# Sheet1.net
KiCad netlist of a schematic drawn in Altium Designer
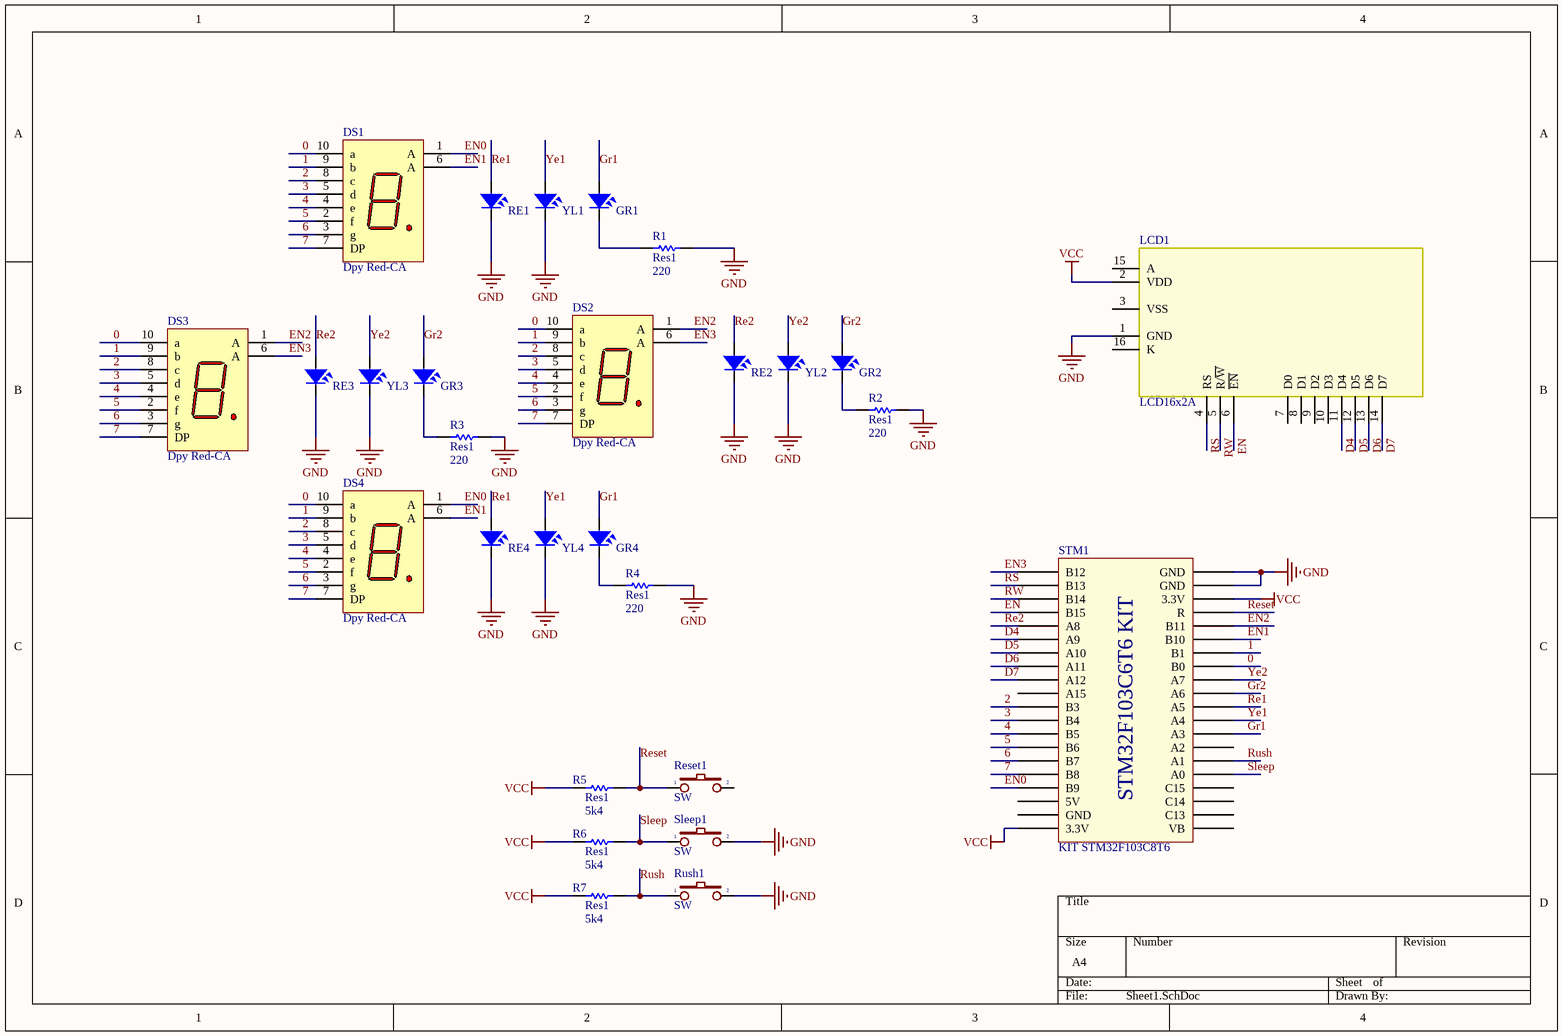
[diagram p0: Sheet1.SchDoc]

(export (version "E")
  (design (tool "Eeschema 10.0.6"))
  (components
    (comp (ref "DS1")
      (value "Dpy Red-CA")
      (footprint "LEDDIP-10")
      (description "7.62 mm Black Surface HER 7-Segment Display: CA, RH DP")
      (fields (field (name "PUBLISHER") "Altium Limited"))
      (libsource (lib "Miscellaneous Devices") (part "Dpy Red-CA"))
    )
    (comp (ref "DS2")
      (value "Dpy Red-CA")
      (footprint "LEDDIP-10")
      (description "7.62 mm Black Surface HER 7-Segment Display: CA, RH DP")
      (fields (field (name "PUBLISHER") "Altium Limited"))
      (libsource (lib "Miscellaneous Devices") (part "Dpy Red-CA"))
    )
    (comp (ref "DS3")
      (value "Dpy Red-CA")
      (footprint "LEDDIP-10")
      (description "7.62 mm Black Surface HER 7-Segment Display: CA, RH DP")
      (fields (field (name "PUBLISHER") "Altium Limited"))
      (libsource (lib "Miscellaneous Devices") (part "Dpy Red-CA"))
    )
    (comp (ref "DS4")
      (value "Dpy Red-CA")
      (footprint "LEDDIP-10")
      (description "7.62 mm Black Surface HER 7-Segment Display: CA, RH DP")
      (fields (field (name "PUBLISHER") "Altium Limited"))
      (libsource (lib "Miscellaneous Devices") (part "Dpy Red-CA"))
    )
    (comp (ref "GR1")
      (value "LED")
      (footprint "LED-3")
      (description "LED Single colour Green and Red")
      (libsource (lib "Thuvien3D") (part "LED"))
    )
    (comp (ref "GR2")
      (value "LED")
      (footprint "LED-3")
      (description "LED Single colour Green and Red")
      (libsource (lib "Thuvien3D") (part "LED"))
    )
    (comp (ref "GR3")
      (value "LED")
      (footprint "LED-3")
      (description "LED Single colour Green and Red")
      (libsource (lib "Thuvien3D") (part "LED"))
    )
    (comp (ref "GR4")
      (value "LED")
      (footprint "LED-3")
      (description "LED Single colour Green and Red")
      (libsource (lib "Thuvien3D") (part "LED"))
    )
    (comp (ref "LCD1")
      (value "LCD16x2A")
      (footprint "LCD16X2")
      (description "LCD dipslay 16 char, 2 line")
      (libsource (lib "Thuvien3D") (part "LCD16x2"))
    )
    (comp (ref "R1")
      (value "Res1")
      (footprint "AXIAL-0.3")
      (description "Resistor")
      (fields (field (name "ALTIUM_VALUE") "220") (field (name "PUBLISHER") "Altium Limited"))
      (libsource (lib "Miscellaneous Devices") (part "Res1"))
    )
    (comp (ref "R2")
      (value "Res1")
      (footprint "AXIAL-0.3")
      (description "Resistor")
      (fields (field (name "ALTIUM_VALUE") "220") (field (name "PUBLISHER") "Altium Limited"))
      (libsource (lib "Miscellaneous Devices") (part "Res1"))
    )
    (comp (ref "R3")
      (value "Res1")
      (footprint "AXIAL-0.3")
      (description "Resistor")
      (fields (field (name "ALTIUM_VALUE") "220") (field (name "PUBLISHER") "Altium Limited"))
      (libsource (lib "Miscellaneous Devices") (part "Res1"))
    )
    (comp (ref "R4")
      (value "Res1")
      (footprint "AXIAL-0.3")
      (description "Resistor")
      (fields (field (name "ALTIUM_VALUE") "220") (field (name "PUBLISHER") "Altium Limited"))
      (libsource (lib "Miscellaneous Devices") (part "Res1"))
    )
    (comp (ref "R5")
      (value "Res1")
      (footprint "AXIAL-0.3")
      (description "Resistor")
      (fields (field (name "ALTIUM_VALUE") "5k4") (field (name "PUBLISHER") "Altium Limited"))
      (libsource (lib "Miscellaneous Devices") (part "Res1"))
    )
    (comp (ref "R6")
      (value "Res1")
      (footprint "AXIAL-0.3")
      (description "Resistor")
      (fields (field (name "ALTIUM_VALUE") "5k4") (field (name "PUBLISHER") "Altium Limited"))
      (libsource (lib "Miscellaneous Devices") (part "Res1"))
    )
    (comp (ref "R7")
      (value "Res1")
      (footprint "AXIAL-0.3")
      (description "Resistor")
      (fields (field (name "ALTIUM_VALUE") "5k4") (field (name "PUBLISHER") "Altium Limited"))
      (libsource (lib "Miscellaneous Devices") (part "Res1"))
    )
    (comp (ref "RE1")
      (value "LED")
      (footprint "LED-3")
      (description "LED Single colour Green and Red")
      (libsource (lib "Thuvien3D") (part "LED"))
    )
    (comp (ref "RE2")
      (value "LED")
      (footprint "LED-3")
      (description "LED Single colour Green and Red")
      (libsource (lib "Thuvien3D") (part "LED"))
    )
    (comp (ref "RE3")
      (value "LED")
      (footprint "LED-3")
      (description "LED Single colour Green and Red")
      (libsource (lib "Thuvien3D") (part "LED"))
    )
    (comp (ref "RE4")
      (value "LED")
      (footprint "LED-3")
      (description "LED Single colour Green and Red")
      (libsource (lib "Thuvien3D") (part "LED"))
    )
    (comp (ref "Reset1")
      (value "SW")
      (footprint "SW2")
      (description "Switch button 2 pin")
      (libsource (lib "Thuvien3D") (part "SW2"))
    )
    (comp (ref "Rush1")
      (value "SW")
      (footprint "SW2")
      (description "Switch button 2 pin")
      (libsource (lib "Thuvien3D") (part "SW2"))
    )
    (comp (ref "Sleep1")
      (value "SW")
      (footprint "SW2")
      (description "Switch button 2 pin")
      (libsource (lib "Thuvien3D") (part "SW2"))
    )
    (comp (ref "STM1")
      (value "KIT STM32F103C8T6")
      (footprint "STM32F103 KIT")
      (description "KIT STM32F103C8T6 Bluepill")
      (libsource (lib "Altium_Lib_by_KhueNguyenCreator") (part "STM32f103 Bluepill"))
    )
    (comp (ref "YL1")
      (value "LED")
      (footprint "LED-3")
      (description "LED Single colour Green and Red")
      (libsource (lib "Thuvien3D") (part "LED"))
    )
    (comp (ref "YL2")
      (value "LED")
      (footprint "LED-3")
      (description "LED Single colour Green and Red")
      (libsource (lib "Thuvien3D") (part "LED"))
    )
    (comp (ref "YL3")
      (value "LED")
      (footprint "LED-3")
      (description "LED Single colour Green and Red")
      (libsource (lib "Thuvien3D") (part "LED"))
    )
    (comp (ref "YL4")
      (value "LED")
      (footprint "LED-3")
      (description "LED Single colour Green and Red")
      (libsource (lib "Thuvien3D") (part "LED"))
    )
  )
  (nets
    (net (code "1") (name "/0") (class "Default")
      (node (ref "DS1") (pin "10") (pinfunction "a_10") (pintype "passive"))
      (node (ref "DS2") (pin "10") (pinfunction "a_10") (pintype "passive"))
      (node (ref "DS3") (pin "10") (pinfunction "a_10") (pintype "passive"))
      (node (ref "DS4") (pin "10") (pinfunction "a_10") (pintype "passive"))
      (node (ref "STM1") (pin "33") (pinfunction "B0_33") (pintype "passive"))
    )
    (net (code "2") (name "/1") (class "Default")
      (node (ref "DS1") (pin "9") (pinfunction "b_9") (pintype "passive"))
      (node (ref "DS2") (pin "9") (pinfunction "b_9") (pintype "passive"))
      (node (ref "DS3") (pin "9") (pinfunction "b_9") (pintype "passive"))
      (node (ref "DS4") (pin "9") (pinfunction "b_9") (pintype "passive"))
      (node (ref "STM1") (pin "34") (pinfunction "B1_34") (pintype "passive"))
    )
    (net (code "3") (name "/2") (class "Default")
      (node (ref "DS1") (pin "8") (pinfunction "c_8") (pintype "passive"))
      (node (ref "DS2") (pin "8") (pinfunction "c_8") (pintype "passive"))
      (node (ref "DS3") (pin "8") (pinfunction "c_8") (pintype "passive"))
      (node (ref "DS4") (pin "8") (pinfunction "c_8") (pintype "passive"))
      (node (ref "STM1") (pin "11") (pinfunction "B3_11") (pintype "passive"))
    )
    (net (code "4") (name "/3") (class "Default")
      (node (ref "DS1") (pin "5") (pinfunction "d_5") (pintype "passive"))
      (node (ref "DS2") (pin "5") (pinfunction "d_5") (pintype "passive"))
      (node (ref "DS4") (pin "5") (pinfunction "d_5") (pintype "passive"))
      (node (ref "STM1") (pin "12") (pinfunction "B4_12") (pintype "passive"))
    )
    (net (code "5") (name "/4") (class "Default")
      (node (ref "DS1") (pin "4") (pinfunction "e_4") (pintype "passive"))
      (node (ref "DS2") (pin "4") (pinfunction "e_4") (pintype "passive"))
      (node (ref "DS3") (pin "4") (pinfunction "e_4") (pintype "passive"))
      (node (ref "DS4") (pin "4") (pinfunction "e_4") (pintype "passive"))
      (node (ref "STM1") (pin "13") (pinfunction "B5_13") (pintype "passive"))
    )
    (net (code "6") (name "/5") (class "Default")
      (node (ref "DS1") (pin "2") (pinfunction "f_2") (pintype "passive"))
      (node (ref "DS2") (pin "2") (pinfunction "f_2") (pintype "passive"))
      (node (ref "DS3") (pin "2") (pinfunction "f_2") (pintype "passive"))
      (node (ref "DS4") (pin "2") (pinfunction "f_2") (pintype "passive"))
      (node (ref "STM1") (pin "14") (pinfunction "B6_14") (pintype "passive"))
    )
    (net (code "7") (name "/6") (class "Default")
      (node (ref "DS1") (pin "3") (pinfunction "g_3") (pintype "passive"))
      (node (ref "DS2") (pin "3") (pinfunction "g_3") (pintype "passive"))
      (node (ref "DS3") (pin "3") (pinfunction "g_3") (pintype "passive"))
      (node (ref "DS4") (pin "3") (pinfunction "g_3") (pintype "passive"))
      (node (ref "STM1") (pin "15") (pinfunction "B7_15") (pintype "passive"))
    )
    (net (code "8") (name "/7") (class "Default")
      (node (ref "DS1") (pin "7") (pinfunction "DP_7") (pintype "passive"))
      (node (ref "DS2") (pin "7") (pinfunction "DP_7") (pintype "passive"))
      (node (ref "DS3") (pin "7") (pinfunction "DP_7") (pintype "passive"))
      (node (ref "DS4") (pin "7") (pinfunction "DP_7") (pintype "passive"))
      (node (ref "STM1") (pin "16") (pinfunction "B8_16") (pintype "passive"))
    )
    (net (code "9") (name "/D4") (class "Default")
      (node (ref "LCD1") (pin "11") (pinfunction "D4_11") (pintype "passive"))
      (node (ref "STM1") (pin "6") (pinfunction "A9_6") (pintype "passive"))
    )
    (net (code "10") (name "/D5") (class "Default")
      (node (ref "LCD1") (pin "12") (pinfunction "D5_12") (pintype "passive"))
      (node (ref "STM1") (pin "7") (pinfunction "A10_7") (pintype "passive"))
    )
    (net (code "11") (name "/D6") (class "Default")
      (node (ref "LCD1") (pin "13") (pinfunction "D6_13") (pintype "passive"))
      (node (ref "STM1") (pin "8") (pinfunction "A11_8") (pintype "passive"))
    )
    (net (code "12") (name "/D7") (class "Default")
      (node (ref "LCD1") (pin "14") (pinfunction "D7_14") (pintype "passive"))
      (node (ref "STM1") (pin "9") (pinfunction "A12_9") (pintype "passive"))
    )
    (net (code "13") (name "/EN") (class "Default")
      (node (ref "LCD1") (pin "6") (pinfunction "~{EN}_6") (pintype "passive"))
      (node (ref "STM1") (pin "4") (pinfunction "B15_4") (pintype "passive"))
    )
    (net (code "14") (name "/EN0") (class "Default")
      (node (ref "DS1") (pin "1") (pinfunction "A_1") (pintype "passive"))
      (node (ref "DS4") (pin "1") (pinfunction "A_1") (pintype "passive"))
      (node (ref "STM1") (pin "17") (pinfunction "B9_17") (pintype "passive"))
    )
    (net (code "15") (name "/EN1") (class "Default")
      (node (ref "DS1") (pin "6") (pinfunction "A_6") (pintype "passive"))
      (node (ref "DS4") (pin "6") (pinfunction "A_6") (pintype "passive"))
      (node (ref "STM1") (pin "35") (pinfunction "B10_35") (pintype "passive"))
    )
    (net (code "16") (name "/EN2") (class "Default")
      (node (ref "DS2") (pin "1") (pinfunction "A_1") (pintype "passive"))
      (node (ref "DS3") (pin "1") (pinfunction "A_1") (pintype "passive"))
      (node (ref "STM1") (pin "36") (pinfunction "B11_36") (pintype "passive"))
    )
    (net (code "17") (name "/EN3") (class "Default")
      (node (ref "DS2") (pin "6") (pinfunction "A_6") (pintype "passive"))
      (node (ref "DS3") (pin "6") (pinfunction "A_6") (pintype "passive"))
      (node (ref "STM1") (pin "1") (pinfunction "B12_1") (pintype "passive"))
    )
    (net (code "18") (name "/Gr1") (class "Default")
      (node (ref "GR1") (pin "1") (pinfunction "1_1") (pintype "passive"))
      (node (ref "GR4") (pin "1") (pinfunction "1_1") (pintype "passive"))
      (node (ref "STM1") (pin "28") (pinfunction "A3_28") (pintype "passive"))
    )
    (net (code "19") (name "/Gr2") (class "Default")
      (node (ref "GR2") (pin "1") (pinfunction "1_1") (pintype "passive"))
      (node (ref "GR3") (pin "1") (pinfunction "1_1") (pintype "passive"))
      (node (ref "STM1") (pin "31") (pinfunction "A6_31") (pintype "passive"))
    )
    (net (code "20") (name "/RS") (class "Default")
      (node (ref "LCD1") (pin "4") (pinfunction "RS_4") (pintype "passive"))
      (node (ref "STM1") (pin "2") (pinfunction "B13_2") (pintype "passive"))
    )
    (net (code "21") (name "/RW") (class "Default")
      (node (ref "LCD1") (pin "5") (pinfunction "R/~{W}_5") (pintype "passive"))
      (node (ref "STM1") (pin "3") (pinfunction "B14_3") (pintype "passive"))
    )
    (net (code "22") (name "/Re1") (class "Default")
      (node (ref "RE1") (pin "1") (pinfunction "1_1") (pintype "passive"))
      (node (ref "RE4") (pin "1") (pinfunction "1_1") (pintype "passive"))
      (node (ref "STM1") (pin "30") (pinfunction "A5_30") (pintype "passive"))
    )
    (net (code "23") (name "/Re2") (class "Default")
      (node (ref "RE2") (pin "1") (pinfunction "1_1") (pintype "passive"))
      (node (ref "RE3") (pin "1") (pinfunction "1_1") (pintype "passive"))
      (node (ref "STM1") (pin "5") (pinfunction "A8_5") (pintype "passive"))
    )
    (net (code "24") (name "/Reset") (class "Default")
      (node (ref "R5") (pin "2") (pinfunction "2_2") (pintype "passive"))
      (node (ref "Reset1") (pin "1") (pinfunction "1_1") (pintype "passive"))
      (node (ref "STM1") (pin "37") (pinfunction "R_37") (pintype "passive"))
    )
    (net (code "25") (name "/Rush") (class "Default")
      (node (ref "R7") (pin "2") (pinfunction "2_2") (pintype "passive"))
      (node (ref "Rush1") (pin "1") (pinfunction "1_1") (pintype "passive"))
      (node (ref "STM1") (pin "26") (pinfunction "A1_26") (pintype "passive"))
    )
    (net (code "26") (name "/Sleep") (class "Default")
      (node (ref "R6") (pin "2") (pinfunction "2_2") (pintype "passive"))
      (node (ref "STM1") (pin "25") (pinfunction "A0_25") (pintype "passive"))
      (node (ref "Sleep1") (pin "1") (pinfunction "1_1") (pintype "passive"))
    )
    (net (code "27") (name "/Ye1") (class "Default")
      (node (ref "STM1") (pin "29") (pinfunction "A4_29") (pintype "passive"))
      (node (ref "YL1") (pin "1") (pinfunction "1_1") (pintype "passive"))
      (node (ref "YL4") (pin "1") (pinfunction "1_1") (pintype "passive"))
    )
    (net (code "28") (name "/Ye2") (class "Default")
      (node (ref "STM1") (pin "32") (pinfunction "A7_32") (pintype "passive"))
      (node (ref "YL2") (pin "1") (pinfunction "1_1") (pintype "passive"))
      (node (ref "YL3") (pin "1") (pinfunction "1_1") (pintype "passive"))
    )
    (net (code "29") (name "/~{3}") (class "Default")
      (node (ref "DS3") (pin "5") (pinfunction "d_5") (pintype "passive"))
    )
    (net (code "30") (name "GND") (class "Default")
      (node (ref "LCD1") (pin "1") (pinfunction "GND_1") (pintype "passive"))
      (node (ref "R1") (pin "2") (pinfunction "2_2") (pintype "passive"))
      (node (ref "R2") (pin "2") (pinfunction "2_2") (pintype "passive"))
      (node (ref "R3") (pin "2") (pinfunction "2_2") (pintype "passive"))
      (node (ref "R4") (pin "2") (pinfunction "2_2") (pintype "passive"))
      (node (ref "RE1") (pin "2") (pinfunction "2_2") (pintype "passive"))
      (node (ref "RE2") (pin "2") (pinfunction "2_2") (pintype "passive"))
      (node (ref "RE3") (pin "2") (pinfunction "2_2") (pintype "passive"))
      (node (ref "RE4") (pin "2") (pinfunction "2_2") (pintype "passive"))
      (node (ref "Rush1") (pin "2") (pinfunction "2_2") (pintype "passive"))
      (node (ref "STM1") (pin "39") (pinfunction "GND_39") (pintype "passive"))
      (node (ref "STM1") (pin "40") (pinfunction "GND_40") (pintype "passive"))
      (node (ref "Sleep1") (pin "2") (pinfunction "2_2") (pintype "passive"))
      (node (ref "YL1") (pin "2") (pinfunction "2_2") (pintype "passive"))
      (node (ref "YL2") (pin "2") (pinfunction "2_2") (pintype "passive"))
      (node (ref "YL3") (pin "2") (pinfunction "2_2") (pintype "passive"))
      (node (ref "YL4") (pin "2") (pinfunction "2_2") (pintype "passive"))
    )
    (net (code "31") (name "Net-(GR1-Pad2)") (class "Default")
      (node (ref "GR1") (pin "2") (pinfunction "2_2") (pintype "passive"))
      (node (ref "R1") (pin "1") (pinfunction "1_1") (pintype "passive"))
    )
    (net (code "32") (name "Net-(GR2-Pad2)") (class "Default")
      (node (ref "GR2") (pin "2") (pinfunction "2_2") (pintype "passive"))
      (node (ref "R2") (pin "1") (pinfunction "1_1") (pintype "passive"))
    )
    (net (code "33") (name "Net-(GR3-Pad2)") (class "Default")
      (node (ref "GR3") (pin "2") (pinfunction "2_2") (pintype "passive"))
      (node (ref "R3") (pin "1") (pinfunction "1_1") (pintype "passive"))
    )
    (net (code "34") (name "Net-(GR4-Pad2)") (class "Default")
      (node (ref "GR4") (pin "2") (pinfunction "2_2") (pintype "passive"))
      (node (ref "R4") (pin "1") (pinfunction "1_1") (pintype "passive"))
    )
    (net (code "35") (name "VCC") (class "Default")
      (node (ref "LCD1") (pin "2") (pinfunction "VDD_2") (pintype "passive"))
      (node (ref "R5") (pin "1") (pinfunction "1_1") (pintype "passive"))
      (node (ref "R6") (pin "1") (pinfunction "1_1") (pintype "passive"))
      (node (ref "R7") (pin "1") (pinfunction "1_1") (pintype "passive"))
      (node (ref "STM1") (pin "20") (pinfunction "3.3V_20") (pintype "passive"))
      (node (ref "STM1") (pin "38") (pinfunction "3.3V_38") (pintype "passive"))
    )
    (net (code "36") (name "unconnected-(LCD1-A-Pad15)") (class "Default")
      (node (ref "LCD1") (pin "15") (pinfunction "A_15") (pintype "passive"))
    )
    (net (code "37") (name "unconnected-(LCD1-D0-Pad7)") (class "Default")
      (node (ref "LCD1") (pin "7") (pinfunction "D0_7") (pintype "passive"))
    )
    (net (code "38") (name "unconnected-(LCD1-D1-Pad8)") (class "Default")
      (node (ref "LCD1") (pin "8") (pinfunction "D1_8") (pintype "passive"))
    )
    (net (code "39") (name "unconnected-(LCD1-D2-Pad9)") (class "Default")
      (node (ref "LCD1") (pin "9") (pinfunction "D2_9") (pintype "passive"))
    )
    (net (code "40") (name "unconnected-(LCD1-D3-Pad10)") (class "Default")
      (node (ref "LCD1") (pin "10") (pinfunction "D3_10") (pintype "passive"))
    )
    (net (code "41") (name "unconnected-(LCD1-K-Pad16)") (class "Default")
      (node (ref "LCD1") (pin "16") (pinfunction "K_16") (pintype "passive"))
    )
    (net (code "42") (name "unconnected-(LCD1-VSS-Pad3)") (class "Default")
      (node (ref "LCD1") (pin "3") (pinfunction "VSS_3") (pintype "passive"))
    )
    (net (code "43") (name "unconnected-(Reset1-Pad2)") (class "Default")
      (node (ref "Reset1") (pin "2") (pinfunction "2_2") (pintype "passive"))
    )
    (net (code "44") (name "unconnected-(STM1-5V-Pad18)") (class "Default")
      (node (ref "STM1") (pin "18") (pinfunction "5V_18") (pintype "passive"))
    )
    (net (code "45") (name "unconnected-(STM1-A2-Pad27)") (class "Default")
      (node (ref "STM1") (pin "27") (pinfunction "A2_27") (pintype "passive"))
    )
    (net (code "46") (name "unconnected-(STM1-A15-Pad10)") (class "Default")
      (node (ref "STM1") (pin "10") (pinfunction "A15_10") (pintype "passive"))
    )
    (net (code "47") (name "unconnected-(STM1-C13-Pad22)") (class "Default")
      (node (ref "STM1") (pin "22") (pinfunction "C13_22") (pintype "passive"))
    )
    (net (code "48") (name "unconnected-(STM1-C14-Pad23)") (class "Default")
      (node (ref "STM1") (pin "23") (pinfunction "C14_23") (pintype "passive"))
    )
    (net (code "49") (name "unconnected-(STM1-C15-Pad24)") (class "Default")
      (node (ref "STM1") (pin "24") (pinfunction "C15_24") (pintype "passive"))
    )
    (net (code "50") (name "unconnected-(STM1-GND-Pad19)") (class "Default")
      (node (ref "STM1") (pin "19") (pinfunction "GND_19") (pintype "passive"))
    )
    (net (code "51") (name "unconnected-(STM1-VB-Pad21)") (class "Default")
      (node (ref "STM1") (pin "21") (pinfunction "VB_21") (pintype "passive"))
    )
  )
)
